# Dimmer.net
KiCad netlist of a schematic drawn in EAGLE
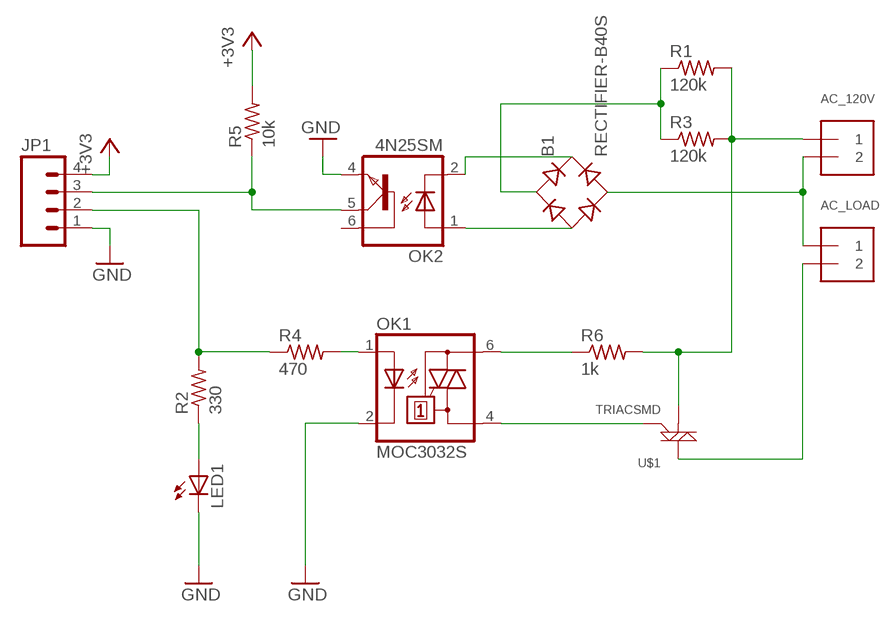
[diagram p0: schematic, sheet 1]

(export (version "E")
  (design (tool "Eeschema 10.0.6"))
  (components
    (comp (ref "AC_120V")
      (value "TERMBLOCK_1X2")
      (footprint "eagle-import:TERMBLOCK_1X2-3.5MM")
      (libsource (lib "eagle-import") (part "TERMBLOCK_1X2"))
    )
    (comp (ref "AC_LOAD")
      (value "TERMBLOCK_1X2")
      (footprint "eagle-import:TERMBLOCK_1X2-3.5MM")
      (libsource (lib "eagle-import") (part "TERMBLOCK_1X2"))
    )
    (comp (ref "B1")
      (value "RECTIFIER-B40S")
      (footprint "eagle-import:B40S")
      (libsource (lib "eagle-import") (part "RECTIFIER-B40S"))
    )
    (comp (ref "JP1")
      (value "M04LONGPADS")
      (footprint "eagle-import:1X04_LONGPADS")
      (libsource (lib "eagle-import") (part "M04LONGPADS"))
    )
    (comp (ref "LED1")
      (value "LEDCHIPLED_0603")
      (footprint "eagle-import:CHIPLED_0603")
      (libsource (lib "eagle-import") (part "LEDCHIPLED_0603"))
    )
    (comp (ref "OK1")
      (value "MOC3032S")
      (footprint "eagle-import:DIL6-SMD")
      (fields (field (name "MF") "FAIRCHILD SEMICONDUCTOR") (field (name "MPN") "MOC3032S-M"))
      (libsource (lib "eagle-import") (part "MOC30S32"))
    )
    (comp (ref "OK2")
      (value "4N25SM")
      (footprint "eagle-import:DIL6-SMD")
      (fields (field (name "MF") "FAIRCHILD SEMICONDUCTOR"))
      (libsource (lib "eagle-import") (part "4N?MS25"))
    )
    (comp (ref "R1")
      (value "120k")
      (footprint "eagle-import:R2512")
      (libsource (lib "eagle-import") (part "R-US_R2512"))
    )
    (comp (ref "R2")
      (value "330")
      (footprint "eagle-import:R0603")
      (libsource (lib "eagle-import") (part "R-US_R0603"))
    )
    (comp (ref "R3")
      (value "120k")
      (footprint "eagle-import:R2512")
      (libsource (lib "eagle-import") (part "R-US_R2512"))
    )
    (comp (ref "R4")
      (value "470")
      (footprint "eagle-import:R0603")
      (libsource (lib "eagle-import") (part "R-US_R0603"))
    )
    (comp (ref "R5")
      (value "10k")
      (footprint "eagle-import:R0603")
      (libsource (lib "eagle-import") (part "R-US_R0603"))
    )
    (comp (ref "R6")
      (value "1k")
      (footprint "eagle-import:R2512")
      (libsource (lib "eagle-import") (part "R-US_R2512"))
    )
    (comp (ref "U$1")
      (value "TRIACSMD")
      (footprint "eagle-import:SOT223")
      (libsource (lib "eagle-import") (part "TRIACSMD"))
    )
  )
  (nets
    (net (code "1") (name "+3V3") (class "Default")
      (node (ref "JP1") (pin "4") (pinfunction "4_4") (pintype "passive"))
      (node (ref "R5") (pin "2") (pinfunction "2_2") (pintype "passive"))
    )
    (net (code "2") (name "GND") (class "Default")
      (node (ref "JP1") (pin "1") (pinfunction "1_1") (pintype "passive"))
      (node (ref "LED1") (pin "C") (pinfunction "C_C") (pintype "passive"))
      (node (ref "OK1") (pin "2") (pinfunction "C_2") (pintype "passive"))
      (node (ref "OK2") (pin "4") (pinfunction "EMI_4") (pintype "passive"))
    )
    (net (code "3") (name "Net-(AC_120V-Pad2)") (class "Default")
      (node (ref "AC_120V") (pin "2") (pinfunction "2_2") (pintype "passive"))
      (node (ref "AC_LOAD") (pin "1") (pinfunction "1_1") (pintype "passive"))
      (node (ref "B1") (pin "AC2") (pinfunction "AC2_AC2") (pintype "passive"))
    )
    (net (code "4") (name "Net-(B1-PadAC1)") (class "Default")
      (node (ref "B1") (pin "AC1") (pinfunction "AC1_AC1") (pintype "passive"))
      (node (ref "R1") (pin "1") (pinfunction "1_1") (pintype "passive"))
      (node (ref "R3") (pin "1") (pinfunction "1_1") (pintype "passive"))
    )
    (net (code "5") (name "Net-(JP1-Pad2)") (class "Default")
      (node (ref "JP1") (pin "2") (pinfunction "2_2") (pintype "passive"))
      (node (ref "R2") (pin "2") (pinfunction "2_2") (pintype "passive"))
      (node (ref "R4") (pin "1") (pinfunction "1_1") (pintype "passive"))
    )
    (net (code "6") (name "Net-(LED1-PadA)") (class "Default")
      (node (ref "LED1") (pin "A") (pinfunction "A_A") (pintype "passive"))
      (node (ref "R2") (pin "1") (pinfunction "1_1") (pintype "passive"))
    )
    (net (code "7") (name "Net-(OK1-A)") (class "Default")
      (node (ref "OK1") (pin "1") (pinfunction "A_1") (pintype "passive"))
      (node (ref "R4") (pin "2") (pinfunction "2_2") (pintype "passive"))
    )
    (net (code "8") (name "Net-(OK1-A1)") (class "Default")
      (node (ref "OK1") (pin "4") (pinfunction "A1_4") (pintype "passive"))
      (node (ref "U$1") (pin "3") (pinfunction "G_3") (pintype "bidirectional"))
    )
    (net (code "9") (name "Net-(OK1-A2)") (class "Default")
      (node (ref "OK1") (pin "6") (pinfunction "A2_6") (pintype "passive"))
      (node (ref "R6") (pin "1") (pinfunction "1_1") (pintype "passive"))
    )
    (net (code "10") (name "Net-(OK2-A)") (class "Default")
      (node (ref "B1") (pin "-") (pinfunction "-_-") (pintype "passive"))
      (node (ref "OK2") (pin "1") (pinfunction "A_1") (pintype "passive"))
    )
    (net (code "11") (name "Net-(OK2-C)") (class "Default")
      (node (ref "B1") (pin "+") (pinfunction "+_+") (pintype "passive"))
      (node (ref "OK2") (pin "2") (pinfunction "C_2") (pintype "passive"))
    )
    (net (code "12") (name "Net-(OK2-COL)") (class "Default")
      (node (ref "JP1") (pin "3") (pinfunction "3_3") (pintype "passive"))
      (node (ref "OK2") (pin "5") (pinfunction "COL_5") (pintype "passive"))
      (node (ref "R5") (pin "1") (pinfunction "1_1") (pintype "passive"))
    )
    (net (code "13") (name "Net-(U$1-M1)") (class "Default")
      (node (ref "AC_120V") (pin "1") (pinfunction "1_1") (pintype "passive"))
      (node (ref "R1") (pin "2") (pinfunction "2_2") (pintype "passive"))
      (node (ref "R3") (pin "2") (pinfunction "2_2") (pintype "passive"))
      (node (ref "R6") (pin "2") (pinfunction "2_2") (pintype "passive"))
      (node (ref "U$1") (pin "1") (pinfunction "M1_1") (pintype "bidirectional"))
    )
    (net (code "14") (name "Net-(U$1-M2)") (class "Default")
      (node (ref "AC_LOAD") (pin "2") (pinfunction "2_2") (pintype "passive"))
      (node (ref "U$1") (pin "2") (pinfunction "M2_2") (pintype "bidirectional"))
    )
    (net (code "15") (name "unconnected-(OK2-BAS-Pad6)") (class "Default")
      (node (ref "OK2") (pin "6") (pinfunction "BAS_6") (pintype "passive"))
    )
  )
)
